# Tilt-NE555-B.net
KiCad netlist of a schematic drawn in EAGLE
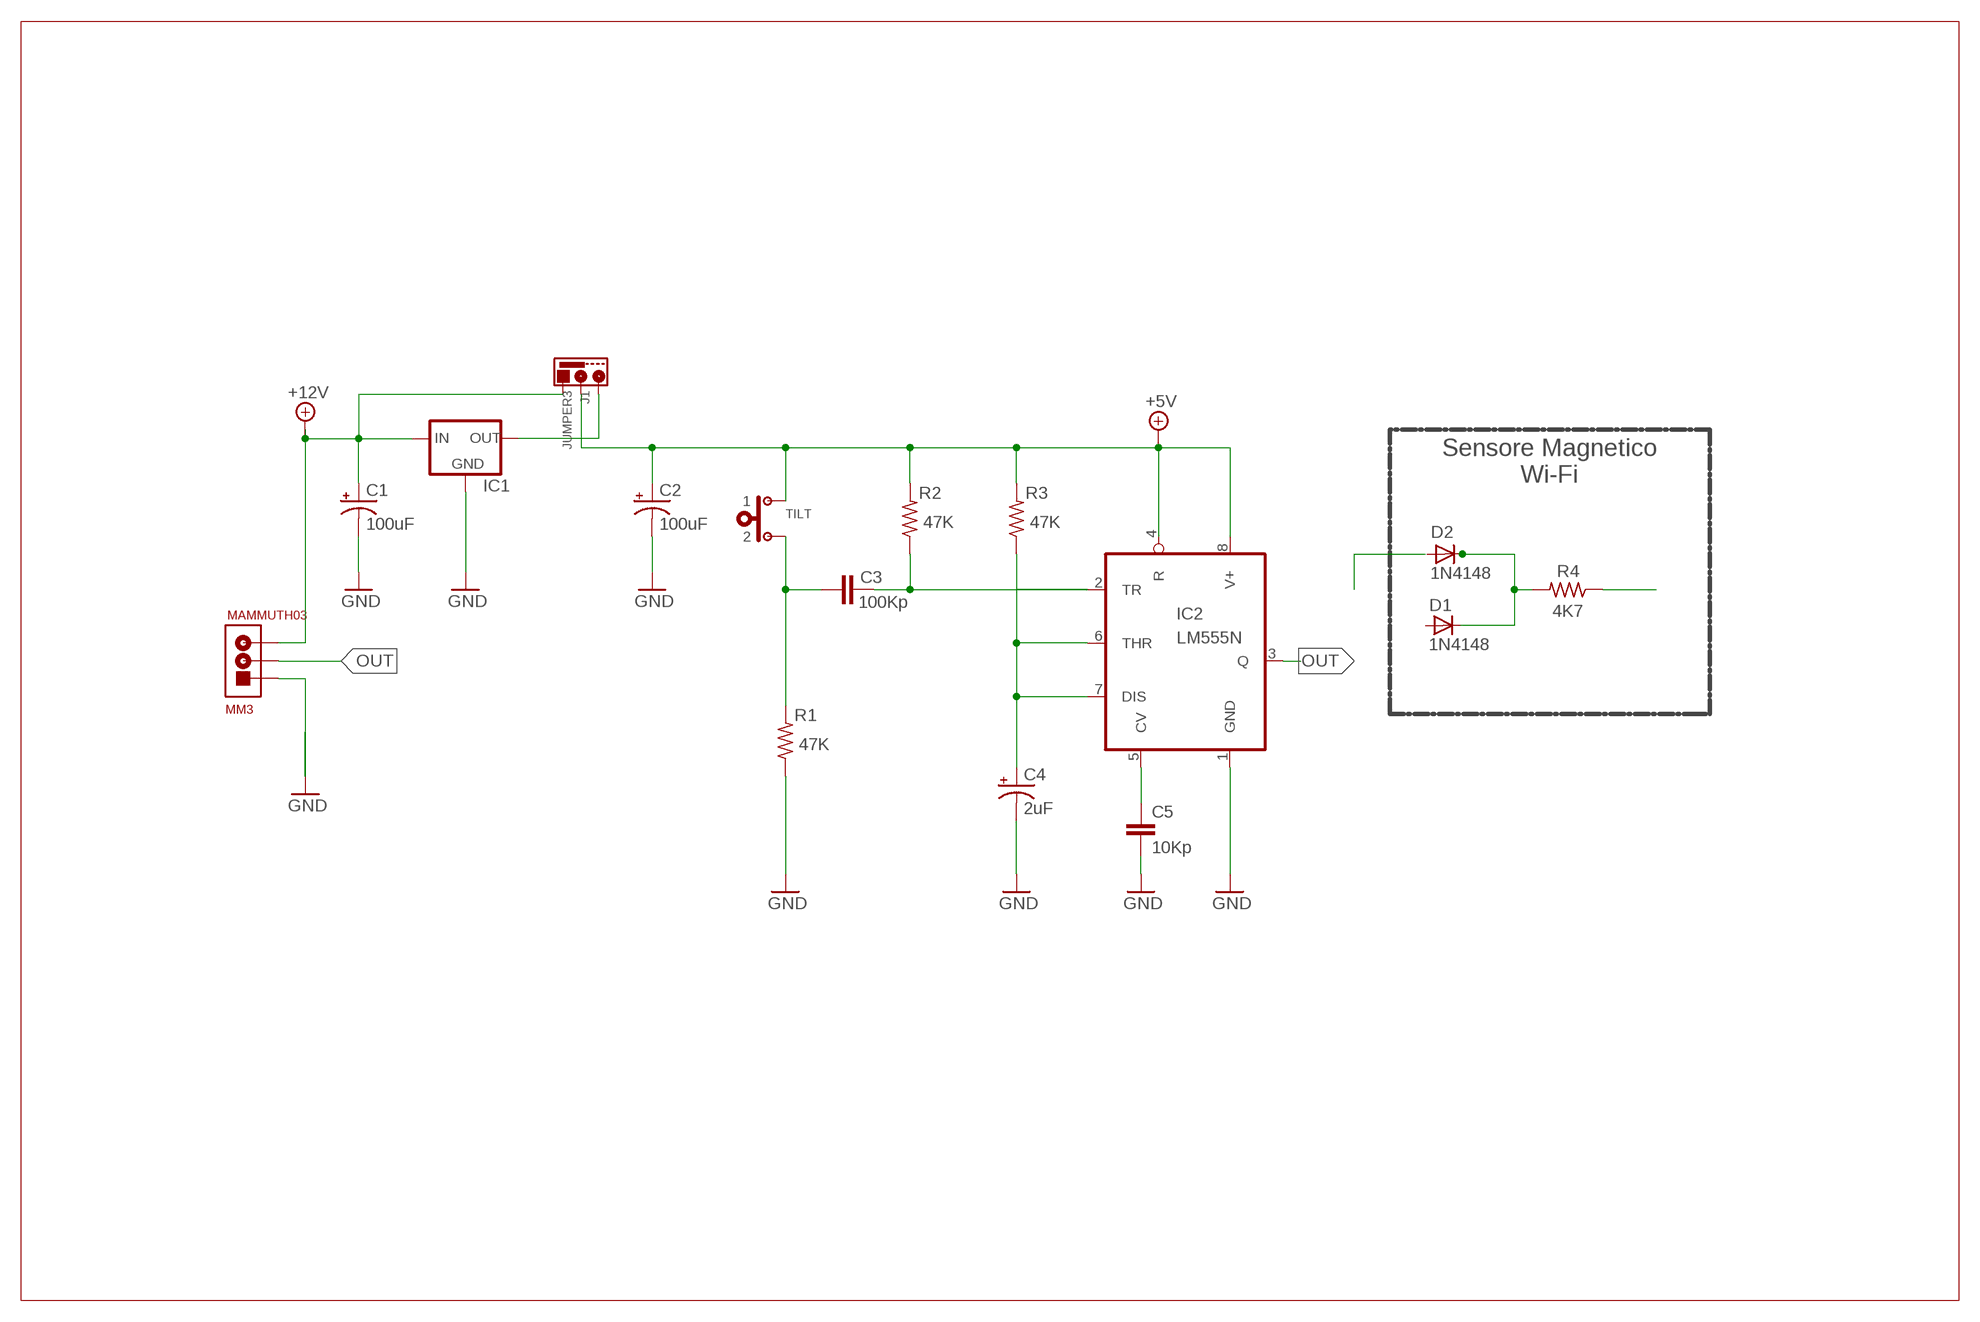
[diagram p0: schematic, sheet 1]

(export (version "E")
  (design (tool "Eeschema 10.0.6"))
  (components
    (comp (ref "C1")
      (value "100uF")
      (footprint "eagle-import:085CS_1AR")
      (libsource (lib "eagle-import") (part "CPOL-US085CS-1AR"))
    )
    (comp (ref "C2")
      (value "100uF")
      (footprint "eagle-import:085CS_1AR")
      (libsource (lib "eagle-import") (part "CPOL-US085CS-1AR"))
    )
    (comp (ref "C3")
      (value "100Kp")
      (footprint "eagle-import:C025-025X050")
      (libsource (lib "eagle-import") (part "C-EU025-025X050"))
    )
    (comp (ref "C4")
      (value "2uF")
      (footprint "eagle-import:085CS_1AR")
      (libsource (lib "eagle-import") (part "CPOL-US085CS-1AR"))
    )
    (comp (ref "C5")
      (value "10Kp")
      (footprint "eagle-import:C025-025X050")
      (libsource (lib "eagle-import") (part "C-EU025-025X050"))
    )
    (comp (ref "D1")
      (value "1N4148")
      (footprint "eagle-import:DO35-10")
      (libsource (lib "eagle-import") (part "1N4148DO35-10"))
    )
    (comp (ref "D2")
      (value "1N4148")
      (footprint "eagle-import:DO35-10")
      (libsource (lib "eagle-import") (part "1N4148DO35-10"))
    )
    (comp (ref "IC1")
      (value "78LXX")
      (footprint "eagle-import:78LXX")
      (libsource (lib "eagle-import") (part "78LXX"))
    )
    (comp (ref "IC2")
      (value "LM555N")
      (footprint "eagle-import:DIL08")
      (libsource (lib "eagle-import") (part "555NLM"))
    )
    (comp (ref "J1")
      (value "JUMPER3")
      (footprint "eagle-import:SIP03")
      (libsource (lib "eagle-import") (part "JUMPER3"))
    )
    (comp (ref "MM3")
      (value "MAMMUTH03")
      (footprint "eagle-import:MAMMUTH03")
      (libsource (lib "eagle-import") (part "MAMMUTH03"))
    )
    (comp (ref "R1")
      (value "47K")
      (footprint "eagle-import:0207_12")
      (libsource (lib "eagle-import") (part "R-US_0207/12"))
    )
    (comp (ref "R2")
      (value "47K")
      (footprint "eagle-import:0207_12")
      (libsource (lib "eagle-import") (part "R-US_0207/12"))
    )
    (comp (ref "R3")
      (value "47K")
      (footprint "eagle-import:0207_12")
      (libsource (lib "eagle-import") (part "R-US_0207/12"))
    )
    (comp (ref "R4")
      (value "4K7")
      (footprint "eagle-import:0207_12")
      (libsource (lib "eagle-import") (part "R-US_0207/12"))
    )
    (comp (ref "TILT")
      (value "PULSANTENO")
      (footprint "eagle-import:SIP02")
      (libsource (lib "eagle-import") (part "PULSANTENO"))
    )
  )
  (nets
    (net (code "1") (name "+5V") (class "Default")
      (node (ref "C2") (pin "+") (pinfunction "+_+") (pintype "passive"))
      (node (ref "IC2") (pin "4") (pinfunction "R_4") (pintype "input"))
      (node (ref "IC2") (pin "8") (pinfunction "V+_8") (pintype "power_in"))
      (node (ref "J1") (pin "1") (pinfunction "1_1") (pintype "bidirectional"))
      (node (ref "R2") (pin "2") (pinfunction "2_2") (pintype "passive"))
      (node (ref "R3") (pin "2") (pinfunction "2_2") (pintype "passive"))
      (node (ref "TILT") (pin "1") (pinfunction "1_1") (pintype "bidirectional"))
    )
    (net (code "2") (name "+12V") (class "Default")
      (node (ref "C1") (pin "+") (pinfunction "+_+") (pintype "passive"))
      (node (ref "IC1") (pin "IN") (pinfunction "IN_IN") (pintype "input"))
      (node (ref "J1") (pin "2") (pinfunction "2_2") (pintype "bidirectional"))
      (node (ref "MM3") (pin "P$3") (pinfunction "3_P$3") (pintype "bidirectional"))
    )
    (net (code "3") (name "GND") (class "Default")
      (node (ref "C1") (pin "-") (pinfunction "-_-") (pintype "passive"))
      (node (ref "C2") (pin "-") (pinfunction "-_-") (pintype "passive"))
      (node (ref "C4") (pin "-") (pinfunction "-_-") (pintype "passive"))
      (node (ref "C5") (pin "2") (pinfunction "2_2") (pintype "passive"))
      (node (ref "IC1") (pin "GND") (pinfunction "GND_GND") (pintype "input"))
      (node (ref "IC2") (pin "1") (pinfunction "GND_1") (pintype "power_in"))
      (node (ref "MM3") (pin "P$1") (pinfunction "1_P$1") (pintype "bidirectional"))
      (node (ref "R1") (pin "1") (pinfunction "1_1") (pintype "passive"))
    )
    (net (code "4") (name "Net-(C3-Pad1)") (class "Default")
      (node (ref "C3") (pin "1") (pinfunction "1_1") (pintype "passive"))
      (node (ref "R1") (pin "2") (pinfunction "2_2") (pintype "passive"))
      (node (ref "TILT") (pin "2") (pinfunction "2_2") (pintype "bidirectional"))
    )
    (net (code "5") (name "Net-(D1-PadC)") (class "Default")
      (node (ref "D1") (pin "C") (pinfunction "C_C") (pintype "passive"))
      (node (ref "D2") (pin "C") (pinfunction "C_C") (pintype "passive"))
      (node (ref "R4") (pin "2") (pinfunction "2_2") (pintype "passive"))
    )
    (net (code "6") (name "Net-(IC1-PadOUT)") (class "Default")
      (node (ref "IC1") (pin "OUT") (pinfunction "OUT_OUT") (pintype "passive"))
      (node (ref "J1") (pin "3") (pinfunction "3_3") (pintype "bidirectional"))
    )
    (net (code "7") (name "Net-(IC2-CV)") (class "Default")
      (node (ref "C5") (pin "1") (pinfunction "1_1") (pintype "passive"))
      (node (ref "IC2") (pin "5") (pinfunction "CV_5") (pintype "input"))
    )
    (net (code "8") (name "Net-(IC2-DIS)") (class "Default")
      (node (ref "C4") (pin "+") (pinfunction "+_+") (pintype "passive"))
      (node (ref "IC2") (pin "6") (pinfunction "THR_6") (pintype "input"))
      (node (ref "IC2") (pin "7") (pinfunction "DIS_7") (pintype "input"))
      (node (ref "R3") (pin "1") (pinfunction "1_1") (pintype "passive"))
    )
    (net (code "9") (name "Net-(IC2-TR)") (class "Default")
      (node (ref "C3") (pin "2") (pinfunction "2_2") (pintype "passive"))
      (node (ref "IC2") (pin "2") (pinfunction "TR_2") (pintype "input"))
      (node (ref "R2") (pin "1") (pinfunction "1_1") (pintype "passive"))
    )
    (net (code "10") (name "OUT") (class "Default")
      (node (ref "IC2") (pin "3") (pinfunction "Q_3") (pintype "output"))
      (node (ref "MM3") (pin "P$2") (pinfunction "2_P$2") (pintype "bidirectional"))
    )
    (net (code "11") (name "unconnected-(D1-PadA)") (class "Default")
      (node (ref "D1") (pin "A") (pinfunction "A_A") (pintype "passive"))
    )
    (net (code "12") (name "unconnected-(D2-PadA)") (class "Default")
      (node (ref "D2") (pin "A") (pinfunction "A_A") (pintype "passive"))
    )
    (net (code "13") (name "unconnected-(R4-Pad1)") (class "Default")
      (node (ref "R4") (pin "1") (pinfunction "1_1") (pintype "passive"))
    )
  )
)
